# Microcontroller.net
KiCad netlist of a schematic drawn in Altium Designer
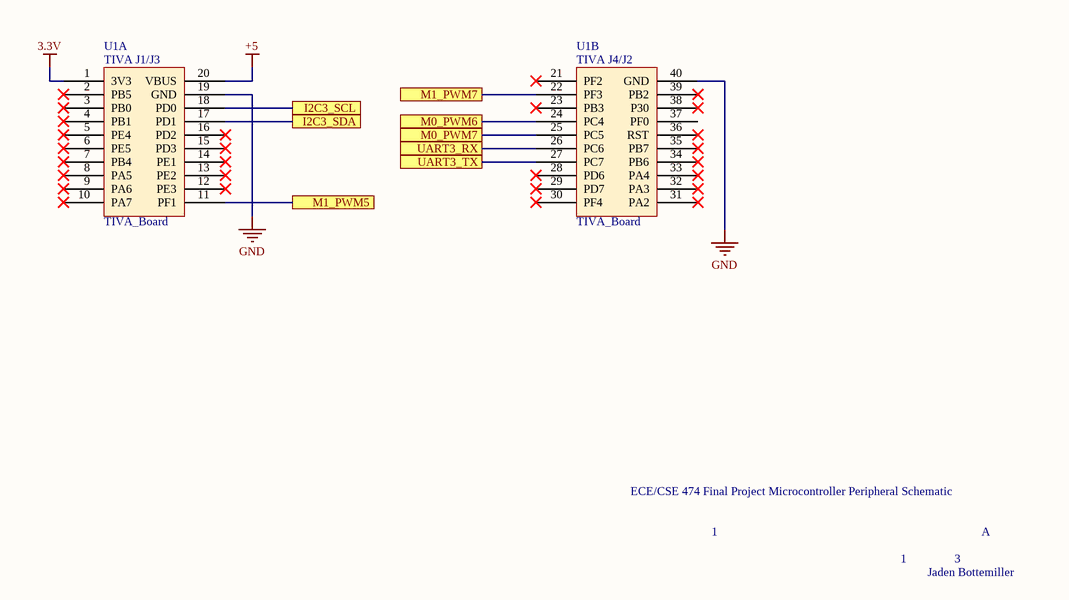
[diagram p0: Microcontroller.SchDoc]

(export (version "E")
  (design (tool "Eeschema 10.0.6"))
  (components
    (comp (ref "U1")
      (value "TIVA_Board")
      (footprint "TIVA_AB")
      (libsource (lib "Quadrotor_Lib") (part "TIVA_Board"))
    )
  )
  (nets
    (net (code "1") (name "+5") (class "Default")
      (node (ref "U1") (pin "20") (pinfunction "VBUS_20") (pintype "passive"))
    )
    (net (code "2") (name "/I2C3_SCL") (class "Default")
      (node (ref "U1") (pin "18") (pinfunction "PD0_18") (pintype "passive"))
    )
    (net (code "3") (name "/I2C3_SDA") (class "Default")
      (node (ref "U1") (pin "17") (pinfunction "PD1_17") (pintype "passive"))
    )
    (net (code "4") (name "/M0_PWM6") (class "Default")
      (node (ref "U1") (pin "24") (pinfunction "PC4_24") (pintype "passive"))
    )
    (net (code "5") (name "/M0_PWM7") (class "Default")
      (node (ref "U1") (pin "25") (pinfunction "PC5_25") (pintype "passive"))
    )
    (net (code "6") (name "/M1_PWM5") (class "Default")
      (node (ref "U1") (pin "11") (pinfunction "PF1_11") (pintype "passive"))
    )
    (net (code "7") (name "/M1_PWM7") (class "Default")
      (node (ref "U1") (pin "22") (pinfunction "PF3_22") (pintype "passive"))
    )
    (net (code "8") (name "/UART3_RX") (class "Default")
      (node (ref "U1") (pin "26") (pinfunction "PC6_26") (pintype "passive"))
    )
    (net (code "9") (name "/UART3_TX") (class "Default")
      (node (ref "U1") (pin "27") (pinfunction "PC7_27") (pintype "passive"))
    )
    (net (code "10") (name "3.3V") (class "Default")
      (node (ref "U1") (pin "1") (pinfunction "3V3_1") (pintype "passive"))
    )
    (net (code "11") (name "GND") (class "Default")
      (node (ref "U1") (pin "19") (pinfunction "GND_19") (pintype "passive"))
      (node (ref "U1") (pin "40") (pinfunction "GND_40") (pintype "passive"))
    )
    (net (code "12") (name "unconnected-(U1A-PA5-Pad8)") (class "Default")
      (node (ref "U1") (pin "8") (pinfunction "PA5_8") (pintype "passive+no_connect"))
    )
    (net (code "13") (name "unconnected-(U1A-PA6-Pad9)") (class "Default")
      (node (ref "U1") (pin "9") (pinfunction "PA6_9") (pintype "passive+no_connect"))
    )
    (net (code "14") (name "unconnected-(U1A-PA7-Pad10)") (class "Default")
      (node (ref "U1") (pin "10") (pinfunction "PA7_10") (pintype "passive+no_connect"))
    )
    (net (code "15") (name "unconnected-(U1A-PB0-Pad3)") (class "Default")
      (node (ref "U1") (pin "3") (pinfunction "PB0_3") (pintype "passive+no_connect"))
    )
    (net (code "16") (name "unconnected-(U1A-PB1-Pad4)") (class "Default")
      (node (ref "U1") (pin "4") (pinfunction "PB1_4") (pintype "passive+no_connect"))
    )
    (net (code "17") (name "unconnected-(U1A-PB4-Pad7)") (class "Default")
      (node (ref "U1") (pin "7") (pinfunction "PB4_7") (pintype "passive+no_connect"))
    )
    (net (code "18") (name "unconnected-(U1A-PB5-Pad2)") (class "Default")
      (node (ref "U1") (pin "2") (pinfunction "PB5_2") (pintype "passive+no_connect"))
    )
    (net (code "19") (name "unconnected-(U1A-PD2-Pad16)") (class "Default")
      (node (ref "U1") (pin "16") (pinfunction "PD2_16") (pintype "passive+no_connect"))
    )
    (net (code "20") (name "unconnected-(U1A-PD3-Pad15)") (class "Default")
      (node (ref "U1") (pin "15") (pinfunction "PD3_15") (pintype "passive+no_connect"))
    )
    (net (code "21") (name "unconnected-(U1A-PE1-Pad14)") (class "Default")
      (node (ref "U1") (pin "14") (pinfunction "PE1_14") (pintype "passive+no_connect"))
    )
    (net (code "22") (name "unconnected-(U1A-PE2-Pad13)") (class "Default")
      (node (ref "U1") (pin "13") (pinfunction "PE2_13") (pintype "passive+no_connect"))
    )
    (net (code "23") (name "unconnected-(U1A-PE3-Pad12)") (class "Default")
      (node (ref "U1") (pin "12") (pinfunction "PE3_12") (pintype "passive+no_connect"))
    )
    (net (code "24") (name "unconnected-(U1A-PE4-Pad5)") (class "Default")
      (node (ref "U1") (pin "5") (pinfunction "PE4_5") (pintype "passive+no_connect"))
    )
    (net (code "25") (name "unconnected-(U1A-PE5-Pad6)") (class "Default")
      (node (ref "U1") (pin "6") (pinfunction "PE5_6") (pintype "passive+no_connect"))
    )
    (net (code "26") (name "unconnected-(U1B-P30-Pad38)") (class "Default")
      (node (ref "U1") (pin "38") (pinfunction "P30_38") (pintype "passive+no_connect"))
    )
    (net (code "27") (name "unconnected-(U1B-PA2-Pad31)") (class "Default")
      (node (ref "U1") (pin "31") (pinfunction "PA2_31") (pintype "passive+no_connect"))
    )
    (net (code "28") (name "unconnected-(U1B-PA3-Pad32)") (class "Default")
      (node (ref "U1") (pin "32") (pinfunction "PA3_32") (pintype "passive+no_connect"))
    )
    (net (code "29") (name "unconnected-(U1B-PA4-Pad33)") (class "Default")
      (node (ref "U1") (pin "33") (pinfunction "PA4_33") (pintype "passive+no_connect"))
    )
    (net (code "30") (name "unconnected-(U1B-PB2-Pad39)") (class "Default")
      (node (ref "U1") (pin "39") (pinfunction "PB2_39") (pintype "passive+no_connect"))
    )
    (net (code "31") (name "unconnected-(U1B-PB3-Pad23)") (class "Default")
      (node (ref "U1") (pin "23") (pinfunction "PB3_23") (pintype "passive+no_connect"))
    )
    (net (code "32") (name "unconnected-(U1B-PB6-Pad34)") (class "Default")
      (node (ref "U1") (pin "34") (pinfunction "PB6_34") (pintype "passive+no_connect"))
    )
    (net (code "33") (name "unconnected-(U1B-PB7-Pad35)") (class "Default")
      (node (ref "U1") (pin "35") (pinfunction "PB7_35") (pintype "passive+no_connect"))
    )
    (net (code "34") (name "unconnected-(U1B-PD6-Pad28)") (class "Default")
      (node (ref "U1") (pin "28") (pinfunction "PD6_28") (pintype "passive+no_connect"))
    )
    (net (code "35") (name "unconnected-(U1B-PD7-Pad29)") (class "Default")
      (node (ref "U1") (pin "29") (pinfunction "PD7_29") (pintype "passive+no_connect"))
    )
    (net (code "36") (name "unconnected-(U1B-PF0-Pad37)") (class "Default")
      (node (ref "U1") (pin "37") (pinfunction "PF0_37") (pintype "passive"))
    )
    (net (code "37") (name "unconnected-(U1B-PF2-Pad21)") (class "Default")
      (node (ref "U1") (pin "21") (pinfunction "PF2_21") (pintype "passive+no_connect"))
    )
    (net (code "38") (name "unconnected-(U1B-PF4-Pad30)") (class "Default")
      (node (ref "U1") (pin "30") (pinfunction "PF4_30") (pintype "passive+no_connect"))
    )
    (net (code "39") (name "unconnected-(U1B-RST-Pad36)") (class "Default")
      (node (ref "U1") (pin "36") (pinfunction "RST_36") (pintype "passive+no_connect"))
    )
  )
)
